# WL-FPGA.net
KiCad netlist of a schematic drawn in Altium Designer
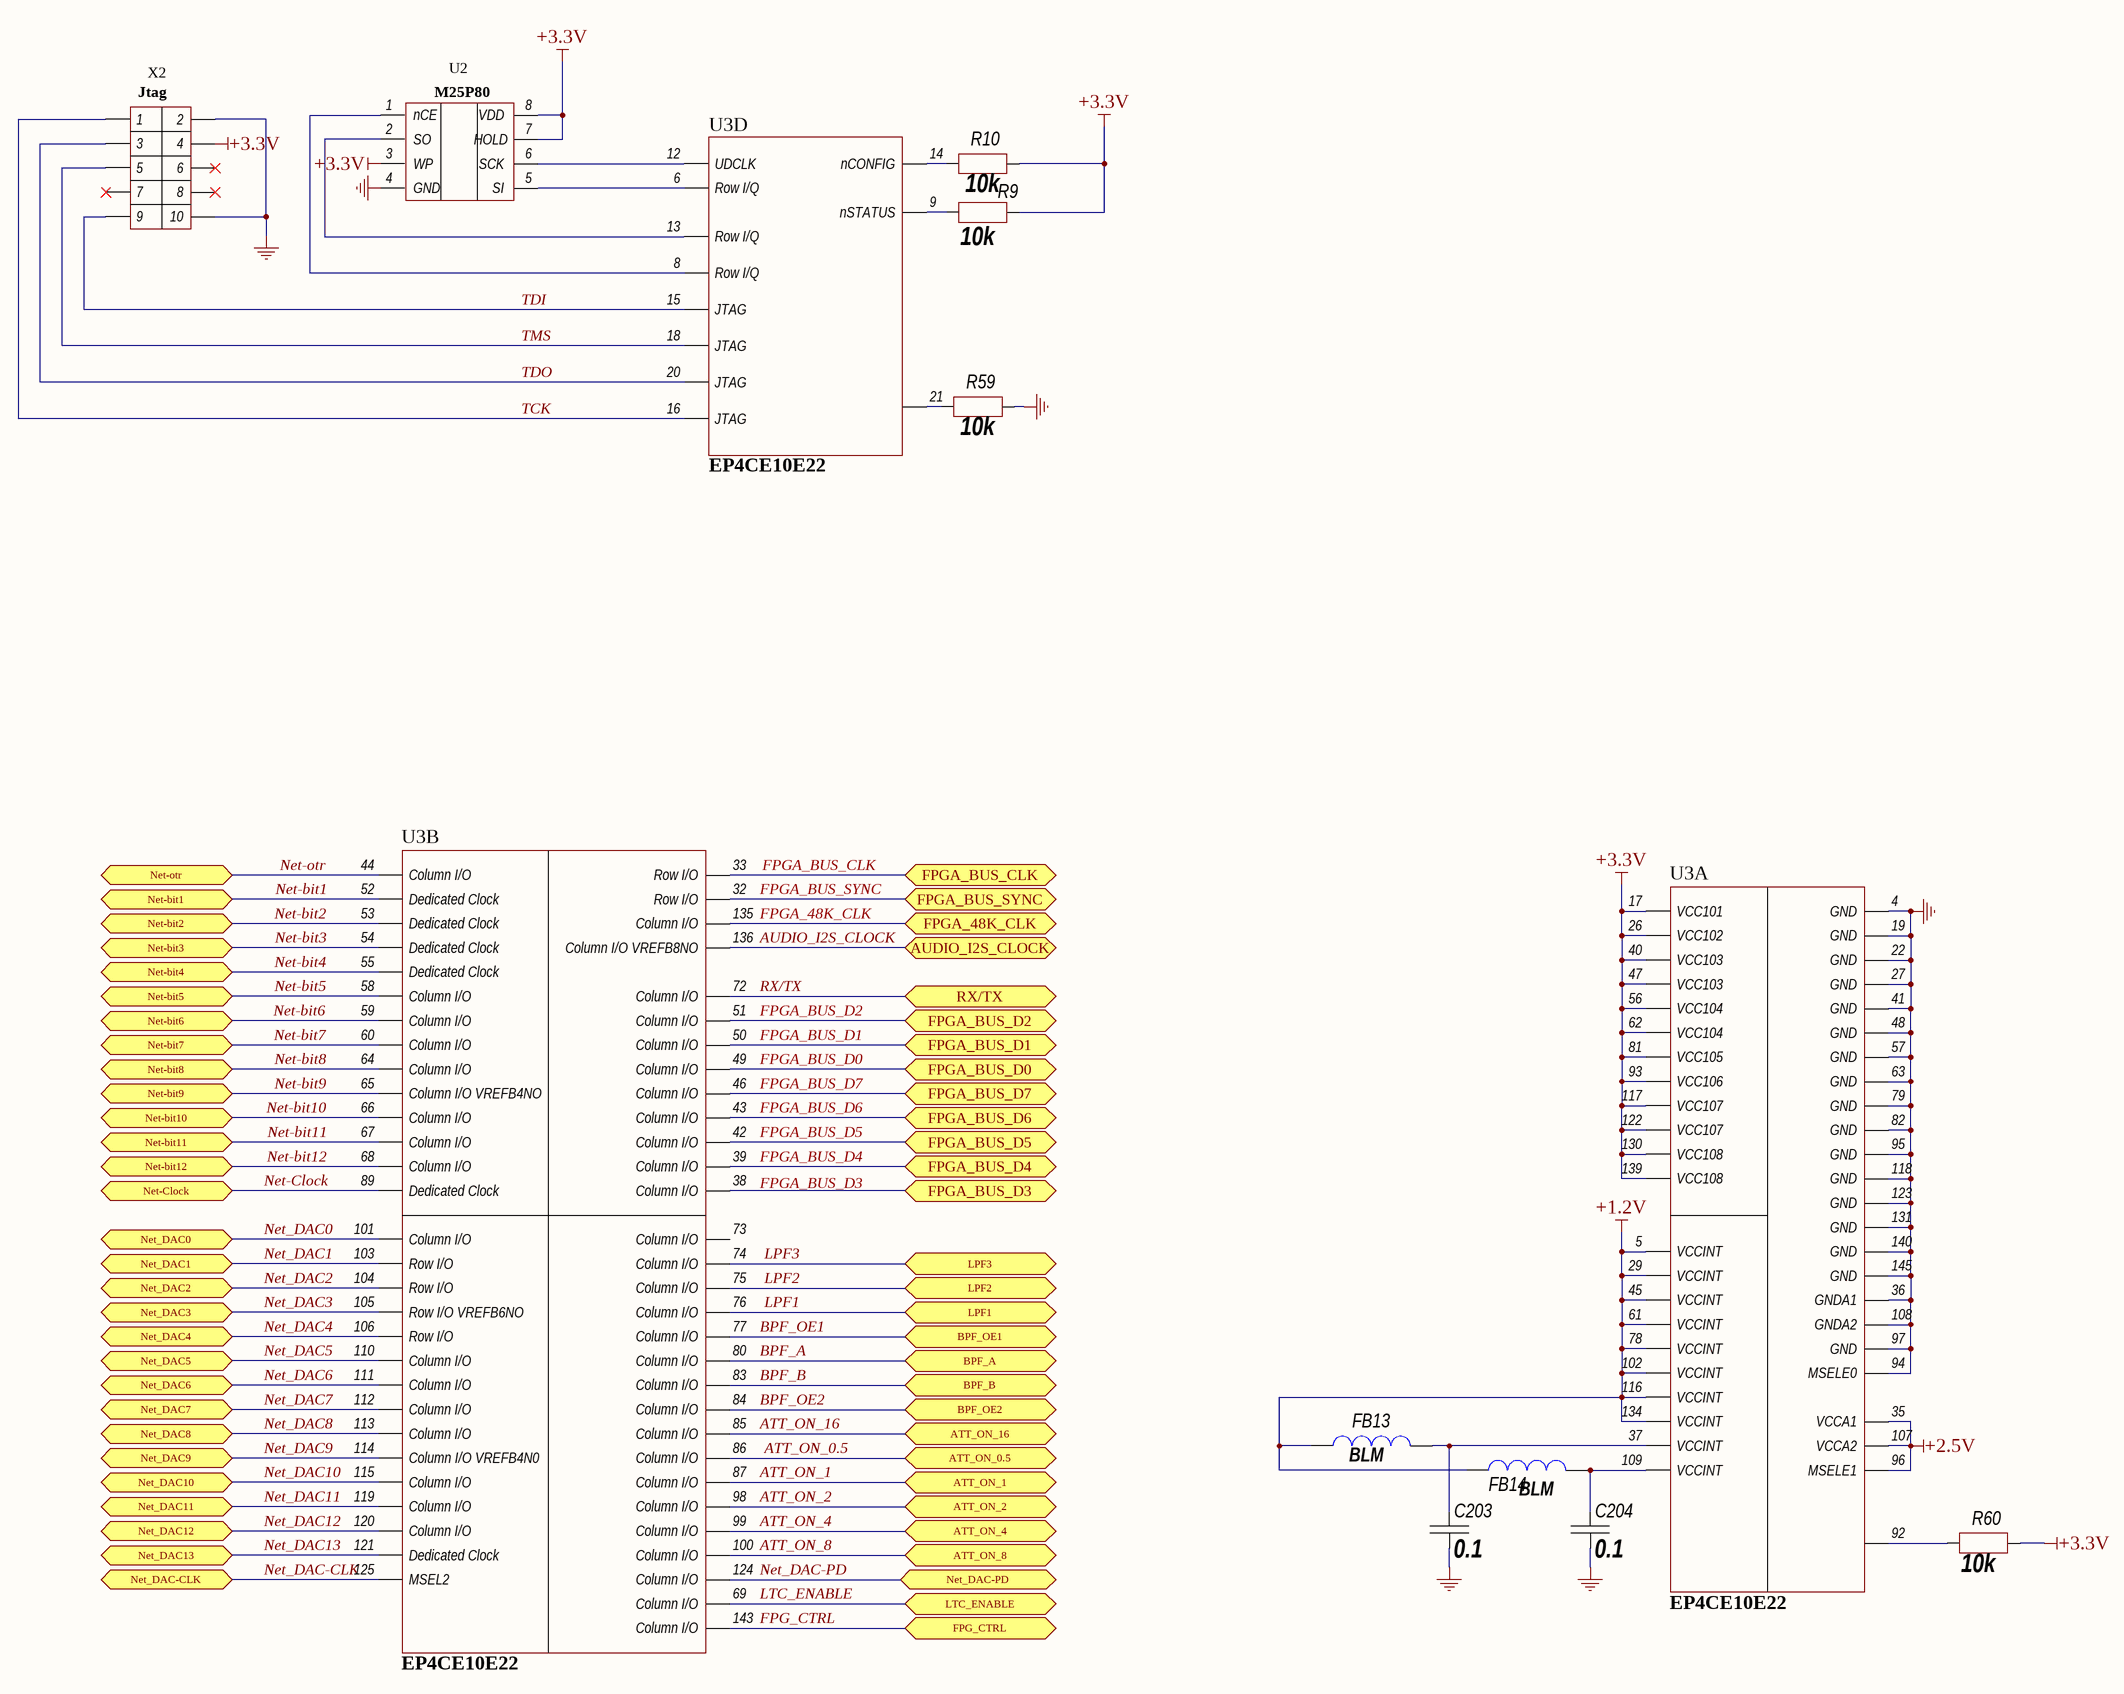
[diagram p0: WL-FPGA.SchDoc]

(export (version "E")
  (design (tool "Eeschema 10.0.6"))
  (components
    (comp (ref "C203")
      (value "0.1")
      (footprint "standard:CH0805C")
      (libsource (lib "Discrete") (part "Capacitor"))
    )
    (comp (ref "C204")
      (value "0.1")
      (footprint "standard:CH0805C")
      (libsource (lib "Discrete") (part "Capacitor"))
    )
    (comp (ref "FB13")
      (value "BLM")
      (footprint "standard:CH0805L")
      (libsource (lib "Discrete") (part "Inductor"))
    )
    (comp (ref "FB14")
      (value "BLM")
      (footprint "standard:CH0805L")
      (libsource (lib "Discrete") (part "Inductor"))
    )
    (comp (ref "R9")
      (value "10k")
      (footprint "standard:CH0805R")
      (libsource (lib "Discrete") (part "Resistor"))
    )
    (comp (ref "R10")
      (value "10k")
      (footprint "standard:CH0805R")
      (libsource (lib "Discrete") (part "Resistor"))
    )
    (comp (ref "R59")
      (value "10k")
      (footprint "standard:CH0805R")
      (libsource (lib "Discrete") (part "Resistor"))
    )
    (comp (ref "R60")
      (value "10k")
      (footprint "standard:CH0805R")
      (libsource (lib "Discrete") (part "Resistor"))
    )
    (comp (ref "U2") (value "M25P80") (footprint "SOIC-8-1") (libsource (lib "Digital") (part "M25P80")))
    (comp (ref "U3")
      (value "EP4CE10E22")
      (footprint "144-QFN")
      (libsource (lib "Digital") (part "EP4CE10E22C8N"))
    )
    (comp (ref "X2") (value "Jtag") (footprint "CON: BH-10") (libsource (lib "Connectors") (part "Jtag")))
  )
  (nets
    (net (code "1") (name "+1.2V") (class "Default")
      (node (ref "FB13") (pin "2") (pinfunction "2_2") (pintype "passive"))
      (node (ref "FB14") (pin "2") (pinfunction "2_2") (pintype "passive"))
      (node (ref "U3") (pin "102") (pinfunction "VCCINT_102") (pintype "passive"))
      (node (ref "U3") (pin "116") (pinfunction "VCCINT_116") (pintype "passive"))
      (node (ref "U3") (pin "134") (pinfunction "VCCINT_134") (pintype "passive"))
      (node (ref "U3") (pin "29") (pinfunction "VCCINT_29") (pintype "passive"))
      (node (ref "U3") (pin "45") (pinfunction "VCCINT_45") (pintype "passive"))
      (node (ref "U3") (pin "5") (pinfunction "VCCINT_5") (pintype "passive"))
      (node (ref "U3") (pin "61") (pinfunction "VCCINT_61") (pintype "passive"))
      (node (ref "U3") (pin "78") (pinfunction "VCCINT_78") (pintype "passive"))
    )
    (net (code "2") (name "+2.5V") (class "Default")
      (node (ref "U3") (pin "107") (pinfunction "VCCA2_107") (pintype "passive"))
      (node (ref "U3") (pin "35") (pinfunction "VCCA1_35") (pintype "passive"))
      (node (ref "U3") (pin "96") (pinfunction "MSELE1_96") (pintype "passive"))
    )
    (net (code "3") (name "+3.3V") (class "Default")
      (node (ref "R10") (pin "1") (pinfunction "1_1") (pintype "passive"))
      (node (ref "R60") (pin "1") (pinfunction "1_1") (pintype "passive"))
      (node (ref "R9") (pin "1") (pinfunction "1_1") (pintype "passive"))
      (node (ref "U2") (pin "3") (pinfunction "WP_3") (pintype "passive"))
      (node (ref "U2") (pin "7") (pinfunction "HOLD_7") (pintype "passive"))
      (node (ref "U2") (pin "8") (pinfunction "VDD_8") (pintype "passive"))
      (node (ref "U3") (pin "117") (pinfunction "VCC107_117") (pintype "passive"))
      (node (ref "U3") (pin "122") (pinfunction "VCC107_122") (pintype "passive"))
      (node (ref "U3") (pin "130") (pinfunction "VCC108_130") (pintype "passive"))
      (node (ref "U3") (pin "139") (pinfunction "VCC108_139") (pintype "passive"))
      (node (ref "U3") (pin "17") (pinfunction "VCC101_17") (pintype "passive"))
      (node (ref "U3") (pin "26") (pinfunction "VCC102_26") (pintype "passive"))
      (node (ref "U3") (pin "40") (pinfunction "VCC103_40") (pintype "passive"))
      (node (ref "U3") (pin "47") (pinfunction "VCC103_47") (pintype "passive"))
      (node (ref "U3") (pin "56") (pinfunction "VCC104_56") (pintype "passive"))
      (node (ref "U3") (pin "62") (pinfunction "VCC104_62") (pintype "passive"))
      (node (ref "U3") (pin "81") (pinfunction "VCC105_81") (pintype "passive"))
      (node (ref "U3") (pin "93") (pinfunction "VCC106_93") (pintype "passive"))
      (node (ref "X2") (pin "4") (pinfunction "4_4") (pintype "power_in"))
    )
    (net (code "4") (name "/ATT_ON_0.5") (class "Default")
      (node (ref "U3") (pin "86") (pinfunction "Column_I/O_86") (pintype "passive"))
    )
    (net (code "5") (name "/ATT_ON_1") (class "Default")
      (node (ref "U3") (pin "87") (pinfunction "Column_I/O_87") (pintype "passive"))
    )
    (net (code "6") (name "/ATT_ON_2") (class "Default")
      (node (ref "U3") (pin "98") (pinfunction "Column_I/O_98") (pintype "passive"))
    )
    (net (code "7") (name "/ATT_ON_4") (class "Default")
      (node (ref "U3") (pin "99") (pinfunction "Column_I/O_99") (pintype "passive"))
    )
    (net (code "8") (name "/ATT_ON_8") (class "Default")
      (node (ref "U3") (pin "100") (pinfunction "Column_I/O_100") (pintype "passive"))
    )
    (net (code "9") (name "/ATT_ON_16") (class "Default")
      (node (ref "U3") (pin "85") (pinfunction "Column_I/O_85") (pintype "passive"))
    )
    (net (code "10") (name "/AUDIO_I2S_CLOCK") (class "Default")
      (node (ref "U3") (pin "136") (pinfunction "Column_I/O_VREFB8NO_136") (pintype "passive"))
    )
    (net (code "11") (name "/BPF_A") (class "Default")
      (node (ref "U3") (pin "80") (pinfunction "Column_I/O_80") (pintype "passive"))
    )
    (net (code "12") (name "/BPF_B") (class "Default")
      (node (ref "U3") (pin "83") (pinfunction "Column_I/O_83") (pintype "passive"))
    )
    (net (code "13") (name "/BPF_OE1") (class "Default")
      (node (ref "U3") (pin "77") (pinfunction "Column_I/O_77") (pintype "passive"))
    )
    (net (code "14") (name "/BPF_OE2") (class "Default")
      (node (ref "U3") (pin "84") (pinfunction "Column_I/O_84") (pintype "passive"))
    )
    (net (code "15") (name "/FPGA_48K_CLK") (class "Default")
      (node (ref "U3") (pin "135") (pinfunction "Column_I/O_135") (pintype "passive"))
    )
    (net (code "16") (name "/FPGA_BUS_CLK") (class "Default")
      (node (ref "U3") (pin "33") (pinfunction "Row_I/O_33") (pintype "passive"))
    )
    (net (code "17") (name "/FPGA_BUS_D0") (class "Default")
      (node (ref "U3") (pin "49") (pinfunction "Column_I/O_49") (pintype "passive"))
    )
    (net (code "18") (name "/FPGA_BUS_D1") (class "Default")
      (node (ref "U3") (pin "50") (pinfunction "Column_I/O_50") (pintype "passive"))
    )
    (net (code "19") (name "/FPGA_BUS_D2") (class "Default")
      (node (ref "U3") (pin "51") (pinfunction "Column_I/O_51") (pintype "passive"))
    )
    (net (code "20") (name "/FPGA_BUS_D3") (class "Default")
      (node (ref "U3") (pin "38") (pinfunction "Column_I/O_38") (pintype "passive"))
    )
    (net (code "21") (name "/FPGA_BUS_D4") (class "Default")
      (node (ref "U3") (pin "39") (pinfunction "Column_I/O_39") (pintype "passive"))
    )
    (net (code "22") (name "/FPGA_BUS_D5") (class "Default")
      (node (ref "U3") (pin "42") (pinfunction "Column_I/O_42") (pintype "passive"))
    )
    (net (code "23") (name "/FPGA_BUS_D6") (class "Default")
      (node (ref "U3") (pin "43") (pinfunction "Column_I/O_43") (pintype "passive"))
    )
    (net (code "24") (name "/FPGA_BUS_D7") (class "Default")
      (node (ref "U3") (pin "46") (pinfunction "Column_I/O_46") (pintype "passive"))
    )
    (net (code "25") (name "/FPGA_BUS_SYNC") (class "Default")
      (node (ref "U3") (pin "32") (pinfunction "Row_I/O_32") (pintype "passive"))
    )
    (net (code "26") (name "/FPG_CTRL") (class "Default")
      (node (ref "U3") (pin "143") (pinfunction "Column_I/O_143") (pintype "passive"))
    )
    (net (code "27") (name "/LPF1") (class "Default")
      (node (ref "U3") (pin "76") (pinfunction "Column_I/O_76") (pintype "passive"))
    )
    (net (code "28") (name "/LPF2") (class "Default")
      (node (ref "U3") (pin "75") (pinfunction "Column_I/O_75") (pintype "passive"))
    )
    (net (code "29") (name "/LPF3") (class "Default")
      (node (ref "U3") (pin "74") (pinfunction "Column_I/O_74") (pintype "passive"))
    )
    (net (code "30") (name "/LTC_ENABLE") (class "Default")
      (node (ref "U3") (pin "69") (pinfunction "Column_I/O_69") (pintype "passive"))
    )
    (net (code "31") (name "/Net-Clock") (class "Default")
      (node (ref "U3") (pin "89") (pinfunction "Dedicated_Clock_89") (pintype "passive"))
    )
    (net (code "32") (name "/Net-bit1") (class "Default")
      (node (ref "U3") (pin "52") (pinfunction "Dedicated_Clock_52") (pintype "passive"))
    )
    (net (code "33") (name "/Net-bit2") (class "Default")
      (node (ref "U3") (pin "53") (pinfunction "Dedicated_Clock_53") (pintype "passive"))
    )
    (net (code "34") (name "/Net-bit3") (class "Default")
      (node (ref "U3") (pin "54") (pinfunction "Dedicated_Clock_54") (pintype "passive"))
    )
    (net (code "35") (name "/Net-bit4") (class "Default")
      (node (ref "U3") (pin "55") (pinfunction "Dedicated_Clock_55") (pintype "passive"))
    )
    (net (code "36") (name "/Net-bit5") (class "Default")
      (node (ref "U3") (pin "58") (pinfunction "Column_I/O_58") (pintype "passive"))
    )
    (net (code "37") (name "/Net-bit6") (class "Default")
      (node (ref "U3") (pin "59") (pinfunction "Column_I/O_59") (pintype "passive"))
    )
    (net (code "38") (name "/Net-bit7") (class "Default")
      (node (ref "U3") (pin "60") (pinfunction "Column_I/O_60") (pintype "passive"))
    )
    (net (code "39") (name "/Net-bit8") (class "Default")
      (node (ref "U3") (pin "64") (pinfunction "Column_I/O_64") (pintype "passive"))
    )
    (net (code "40") (name "/Net-bit9") (class "Default")
      (node (ref "U3") (pin "65") (pinfunction "Column_I/O_VREFB4NO_65") (pintype "passive"))
    )
    (net (code "41") (name "/Net-bit10") (class "Default")
      (node (ref "U3") (pin "66") (pinfunction "Column_I/O_66") (pintype "passive"))
    )
    (net (code "42") (name "/Net-bit11") (class "Default")
      (node (ref "U3") (pin "67") (pinfunction "Column_I/O_67") (pintype "passive"))
    )
    (net (code "43") (name "/Net-bit12") (class "Default")
      (node (ref "U3") (pin "68") (pinfunction "Column_I/O_68") (pintype "passive"))
    )
    (net (code "44") (name "/Net-otr") (class "Default")
      (node (ref "U3") (pin "44") (pinfunction "Column_I/O_44") (pintype "passive"))
    )
    (net (code "45") (name "/Net_DAC-CLK") (class "Default")
      (node (ref "U3") (pin "125") (pinfunction "MSEL2_125") (pintype "passive"))
    )
    (net (code "46") (name "/Net_DAC-PD") (class "Default")
      (node (ref "U3") (pin "124") (pinfunction "Column_I/O_124") (pintype "passive"))
    )
    (net (code "47") (name "/Net_DAC0") (class "Default")
      (node (ref "U3") (pin "101") (pinfunction "Column_I/O_101") (pintype "passive"))
    )
    (net (code "48") (name "/Net_DAC1") (class "Default")
      (node (ref "U3") (pin "103") (pinfunction "Row_I/O_103") (pintype "passive"))
    )
    (net (code "49") (name "/Net_DAC2") (class "Default")
      (node (ref "U3") (pin "104") (pinfunction "Row_I/O_104") (pintype "passive"))
    )
    (net (code "50") (name "/Net_DAC3") (class "Default")
      (node (ref "U3") (pin "105") (pinfunction "Row_I/O_VREFB6NO_105") (pintype "passive"))
    )
    (net (code "51") (name "/Net_DAC4") (class "Default")
      (node (ref "U3") (pin "106") (pinfunction "Row_I/O_106") (pintype "passive"))
    )
    (net (code "52") (name "/Net_DAC5") (class "Default")
      (node (ref "U3") (pin "110") (pinfunction "Column_I/O_110") (pintype "passive"))
    )
    (net (code "53") (name "/Net_DAC6") (class "Default")
      (node (ref "U3") (pin "111") (pinfunction "Column_I/O_111") (pintype "passive"))
    )
    (net (code "54") (name "/Net_DAC7") (class "Default")
      (node (ref "U3") (pin "112") (pinfunction "Column_I/O_112") (pintype "passive"))
    )
    (net (code "55") (name "/Net_DAC8") (class "Default")
      (node (ref "U3") (pin "113") (pinfunction "Column_I/O_113") (pintype "passive"))
    )
    (net (code "56") (name "/Net_DAC9") (class "Default")
      (node (ref "U3") (pin "114") (pinfunction "Column_I/O_VREFB4N0_114") (pintype "passive"))
    )
    (net (code "57") (name "/Net_DAC10") (class "Default")
      (node (ref "U3") (pin "115") (pinfunction "Column_I/O_115") (pintype "passive"))
    )
    (net (code "58") (name "/Net_DAC11") (class "Default")
      (node (ref "U3") (pin "119") (pinfunction "Column_I/O_119") (pintype "passive"))
    )
    (net (code "59") (name "/Net_DAC12") (class "Default")
      (node (ref "U3") (pin "120") (pinfunction "Column_I/O_120") (pintype "passive"))
    )
    (net (code "60") (name "/Net_DAC13") (class "Default")
      (node (ref "U3") (pin "121") (pinfunction "Dedicated_Clock_121") (pintype "passive"))
    )
    (net (code "61") (name "/RX{slash}TX") (class "Default")
      (node (ref "U3") (pin "72") (pinfunction "Column_I/O_72") (pintype "passive"))
    )
    (net (code "62") (name "/TCK") (class "Default")
      (node (ref "U3") (pin "16") (pinfunction "JTAG_16") (pintype "passive"))
      (node (ref "X2") (pin "1") (pinfunction "1_1") (pintype "passive"))
    )
    (net (code "63") (name "/TDI") (class "Default")
      (node (ref "U3") (pin "15") (pinfunction "JTAG_15") (pintype "power_in"))
      (node (ref "X2") (pin "9") (pinfunction "9_9") (pintype "power_in"))
    )
    (net (code "64") (name "/TDO") (class "Default")
      (node (ref "U3") (pin "20") (pinfunction "JTAG_20") (pintype "passive"))
      (node (ref "X2") (pin "3") (pinfunction "3_3") (pintype "passive"))
    )
    (net (code "65") (name "/TMS") (class "Default")
      (node (ref "U3") (pin "18") (pinfunction "JTAG_18") (pintype "passive"))
      (node (ref "X2") (pin "5") (pinfunction "5_5") (pintype "power_in"))
    )
    (net (code "66") (name "GND") (class "Default")
      (node (ref "C203") (pin "1") (pinfunction "1_1") (pintype "power_in"))
      (node (ref "C204") (pin "1") (pinfunction "1_1") (pintype "power_in"))
      (node (ref "R59") (pin "1") (pinfunction "1_1") (pintype "passive"))
      (node (ref "U2") (pin "4") (pinfunction "GND_4") (pintype "passive"))
      (node (ref "U3") (pin "108") (pinfunction "GNDA2_108") (pintype "passive"))
      (node (ref "U3") (pin "118") (pinfunction "GND_118") (pintype "passive"))
      (node (ref "U3") (pin "123") (pinfunction "GND_123") (pintype "passive"))
      (node (ref "U3") (pin "131") (pinfunction "GND_131") (pintype "passive"))
      (node (ref "U3") (pin "140") (pinfunction "GND_140") (pintype "passive"))
      (node (ref "U3") (pin "145") (pinfunction "GND_145") (pintype "passive"))
      (node (ref "U3") (pin "19") (pinfunction "GND_19") (pintype "passive"))
      (node (ref "U3") (pin "22") (pinfunction "GND_22") (pintype "passive"))
      (node (ref "U3") (pin "27") (pinfunction "GND_27") (pintype "passive"))
      (node (ref "U3") (pin "36") (pinfunction "GNDA1_36") (pintype "passive"))
      (node (ref "U3") (pin "4") (pinfunction "GND_4") (pintype "passive"))
      (node (ref "U3") (pin "41") (pinfunction "GND_41") (pintype "passive"))
      (node (ref "U3") (pin "48") (pinfunction "GND_48") (pintype "passive"))
      (node (ref "U3") (pin "57") (pinfunction "GND_57") (pintype "passive"))
      (node (ref "U3") (pin "63") (pinfunction "GND_63") (pintype "passive"))
      (node (ref "U3") (pin "79") (pinfunction "GND_79") (pintype "passive"))
      (node (ref "U3") (pin "82") (pinfunction "GND_82") (pintype "passive"))
      (node (ref "U3") (pin "94") (pinfunction "MSELE0_94") (pintype "passive"))
      (node (ref "U3") (pin "95") (pinfunction "GND_95") (pintype "passive"))
      (node (ref "U3") (pin "97") (pinfunction "GND_97") (pintype "passive"))
      (node (ref "X2") (pin "10") (pinfunction "10_10") (pintype "power_in"))
      (node (ref "X2") (pin "2") (pinfunction "2_2") (pintype "power_in"))
    )
    (net (code "67") (name "Net-(C203-Pad2)") (class "Default")
      (node (ref "C203") (pin "2") (pinfunction "2_2") (pintype "power_in"))
      (node (ref "FB13") (pin "1") (pinfunction "1_1") (pintype "passive"))
      (node (ref "U3") (pin "37") (pinfunction "VCCINT_37") (pintype "passive"))
    )
    (net (code "68") (name "Net-(C204-Pad2)") (class "Default")
      (node (ref "C204") (pin "2") (pinfunction "2_2") (pintype "power_in"))
      (node (ref "FB14") (pin "1") (pinfunction "1_1") (pintype "passive"))
      (node (ref "U3") (pin "109") (pinfunction "VCCINT_109") (pintype "passive"))
    )
    (net (code "69") (name "Net-(R60-Pad2)") (class "Default")
      (node (ref "R60") (pin "2") (pinfunction "2_2") (pintype "passive"))
      (node (ref "U3") (pin "92") (pintype "passive"))
    )
    (net (code "70") (name "Net-(U2-SCK)") (class "Default")
      (node (ref "U2") (pin "6") (pinfunction "SCK_6") (pintype "passive"))
      (node (ref "U3") (pin "12") (pinfunction "UDCLK_12") (pintype "passive"))
    )
    (net (code "71") (name "Net-(U2-SI)") (class "Default")
      (node (ref "U2") (pin "5") (pinfunction "SI_5") (pintype "passive"))
      (node (ref "U3") (pin "6") (pinfunction "Row_I/Q_6") (pintype "passive"))
    )
    (net (code "72") (name "Net-(U2-SO)") (class "Default")
      (node (ref "U2") (pin "2") (pinfunction "SO_2") (pintype "passive"))
      (node (ref "U3") (pin "13") (pinfunction "Row_I/Q_13") (pintype "passive"))
    )
    (net (code "73") (name "Net-(U2-nCE)") (class "Default")
      (node (ref "U2") (pin "1") (pinfunction "nCE_1") (pintype "passive"))
      (node (ref "U3") (pin "8") (pinfunction "Row_I/Q_8") (pintype "passive"))
    )
    (net (code "74") (name "Net-(U3D-nCE)") (class "Default")
      (node (ref "R59") (pin "2") (pinfunction "2_2") (pintype "passive"))
      (node (ref "U3") (pin "21") (pinfunction "nCE_21") (pintype "passive"))
    )
    (net (code "75") (name "Net-(U3D-nCONFIG)") (class "Default")
      (node (ref "R10") (pin "2") (pinfunction "2_2") (pintype "passive"))
      (node (ref "U3") (pin "14") (pinfunction "nCONFIG_14") (pintype "passive"))
    )
    (net (code "76") (name "Net-(U3D-nSTATUS)") (class "Default")
      (node (ref "R9") (pin "2") (pinfunction "2_2") (pintype "passive"))
      (node (ref "U3") (pin "9") (pinfunction "nSTATUS_9") (pintype "passive"))
    )
    (net (code "77") (name "unconnected-(U3B-Column_I{slash}O-Pad73)") (class "Default")
      (node (ref "U3") (pin "73") (pinfunction "Column_I/O_73") (pintype "passive"))
    )
    (net (code "78") (name "unconnected-(X2-Pad6)") (class "Default")
      (node (ref "X2") (pin "6") (pinfunction "6_6") (pintype "power_in+no_connect"))
    )
    (net (code "79") (name "unconnected-(X2-Pad7)") (class "Default")
      (node (ref "X2") (pin "7") (pinfunction "7_7") (pintype "power_in+no_connect"))
    )
    (net (code "80") (name "unconnected-(X2-Pad8)") (class "Default")
      (node (ref "X2") (pin "8") (pinfunction "8_8") (pintype "power_in+no_connect"))
    )
  )
)
